# Sens_BMP085.net
KiCad netlist of a schematic drawn in EAGLE
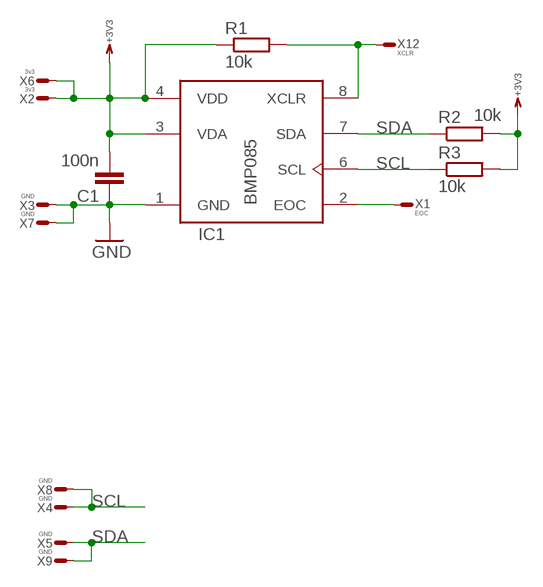
[diagram p0: schematic, sheet 1]

(export (version "E")
  (design (tool "Eeschema 10.0.6"))
  (components
    (comp (ref "C1")
      (value "100n")
      (footprint "eagle-import:0603")
      (libsource (lib "eagle-import") (part "C0603"))
    )
    (comp (ref "IC1")
      (value "BMP085")
      (footprint "eagle-import:LCC8")
      (libsource (lib "eagle-import") (part "BMP085"))
    )
    (comp (ref "R1")
      (value "10k")
      (footprint "eagle-import:0603")
      (libsource (lib "eagle-import") (part "R0603"))
    )
    (comp (ref "R2")
      (value "10k")
      (footprint "eagle-import:0603")
      (libsource (lib "eagle-import") (part "R0603"))
    )
    (comp (ref "R3")
      (value "10k")
      (footprint "eagle-import:0603")
      (libsource (lib "eagle-import") (part "R0603"))
    )
    (comp (ref "X1")
      (value "EOC")
      (footprint "eagle-import:S1.27R")
      (libsource (lib "eagle-import") (part "WIREPADR"))
    )
    (comp (ref "X2")
      (value "3v3")
      (footprint "eagle-import:T1.6_0.9")
      (libsource (lib "eagle-import") (part "WIREPADT1.6/0.9"))
    )
    (comp (ref "X3")
      (value "GND")
      (footprint "eagle-import:T1.6_0.9")
      (libsource (lib "eagle-import") (part "WIREPADT1.6/0.9"))
    )
    (comp (ref "X4")
      (value "GND")
      (footprint "eagle-import:T1.6_0.9")
      (libsource (lib "eagle-import") (part "WIREPADT1.6/0.9"))
    )
    (comp (ref "X5")
      (value "GND")
      (footprint "eagle-import:T1.6_0.9")
      (libsource (lib "eagle-import") (part "WIREPADT1.6/0.9"))
    )
    (comp (ref "X6")
      (value "3v3")
      (footprint "eagle-import:T1.6_0.9")
      (libsource (lib "eagle-import") (part "WIREPADT1.6/0.9"))
    )
    (comp (ref "X7")
      (value "GND")
      (footprint "eagle-import:T1.6_0.9")
      (libsource (lib "eagle-import") (part "WIREPADT1.6/0.9"))
    )
    (comp (ref "X8")
      (value "GND")
      (footprint "eagle-import:T1.6_0.9")
      (libsource (lib "eagle-import") (part "WIREPADT1.6/0.9"))
    )
    (comp (ref "X9")
      (value "GND")
      (footprint "eagle-import:T1.6_0.9")
      (libsource (lib "eagle-import") (part "WIREPADT1.6/0.9"))
    )
    (comp (ref "X12")
      (value "XCLR")
      (footprint "eagle-import:S1.27R")
      (libsource (lib "eagle-import") (part "WIREPADR"))
    )
  )
  (nets
    (net (code "1") (name "+3V3") (class "Default")
      (node (ref "C1") (pin "2") (pinfunction "2_2") (pintype "passive"))
      (node (ref "IC1") (pin "3") (pinfunction "VDA_3") (pintype "input"))
      (node (ref "IC1") (pin "4") (pinfunction "VDD_4") (pintype "input"))
      (node (ref "R1") (pin "1") (pinfunction "1_1") (pintype "passive"))
      (node (ref "R2") (pin "2") (pinfunction "2_2") (pintype "passive"))
      (node (ref "R3") (pin "2") (pinfunction "2_2") (pintype "passive"))
      (node (ref "X2") (pin "1") (pinfunction "S_1") (pintype "passive"))
      (node (ref "X6") (pin "1") (pinfunction "S_1") (pintype "passive"))
    )
    (net (code "2") (name "/SCL") (class "Default")
      (node (ref "IC1") (pin "6") (pinfunction "SCL_6") (pintype "input"))
      (node (ref "R3") (pin "1") (pinfunction "1_1") (pintype "passive"))
      (node (ref "X4") (pin "1") (pinfunction "S_1") (pintype "passive"))
      (node (ref "X8") (pin "1") (pinfunction "S_1") (pintype "passive"))
    )
    (net (code "3") (name "/SDA") (class "Default")
      (node (ref "IC1") (pin "7") (pinfunction "SDA_7") (pintype "bidirectional"))
      (node (ref "R2") (pin "1") (pinfunction "1_1") (pintype "passive"))
      (node (ref "X5") (pin "1") (pinfunction "S_1") (pintype "passive"))
      (node (ref "X9") (pin "1") (pinfunction "S_1") (pintype "passive"))
    )
    (net (code "4") (name "GND") (class "Default")
      (node (ref "C1") (pin "1") (pinfunction "1_1") (pintype "passive"))
      (node (ref "IC1") (pin "1") (pinfunction "GND_1") (pintype "input"))
      (node (ref "X3") (pin "1") (pinfunction "S_1") (pintype "passive"))
      (node (ref "X7") (pin "1") (pinfunction "S_1") (pintype "passive"))
    )
    (net (code "5") (name "Net-(IC1-EOC)") (class "Default")
      (node (ref "IC1") (pin "2") (pinfunction "EOC_2") (pintype "output"))
      (node (ref "X1") (pin "1") (pinfunction "S_1") (pintype "passive"))
    )
    (net (code "6") (name "Net-(IC1-XCLR)") (class "Default")
      (node (ref "IC1") (pin "8") (pinfunction "XCLR_8") (pintype "input"))
      (node (ref "R1") (pin "2") (pinfunction "2_2") (pintype "passive"))
      (node (ref "X12") (pin "1") (pinfunction "S_1") (pintype "passive"))
    )
  )
)
